# Solenoid_con.net
KiCad netlist of a schematic drawn in EAGLE
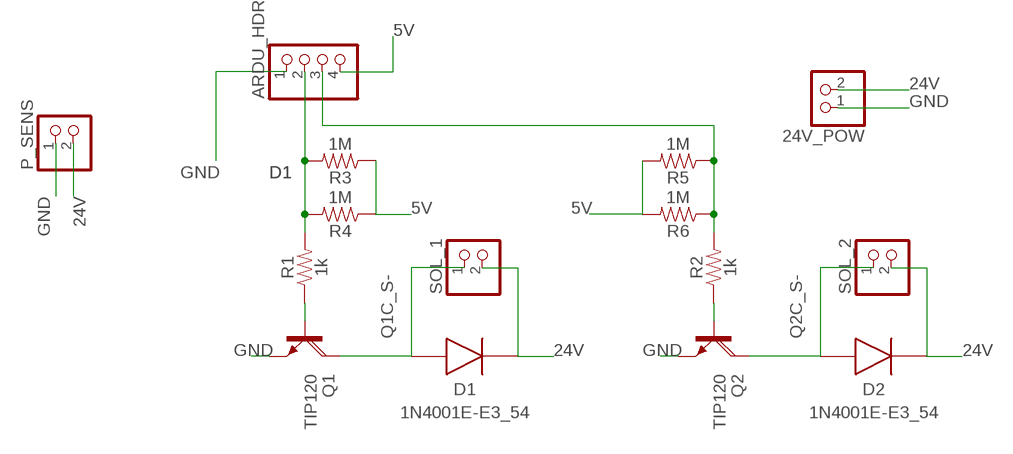
[diagram p0: schematic, sheet 1]

(export (version "E")
  (design (tool "Eeschema 10.0.6"))
  (components
    (comp (ref "24V_POW")
      (value "PINHD-1X2")
      (footprint "eagle-import:1X02")
      (libsource (lib "eagle-import") (part "PINHD-1X2"))
    )
    (comp (ref "ARDU_HDR")
      (value "PINHD-1X4")
      (footprint "eagle-import:1X04")
      (libsource (lib "eagle-import") (part "PINHD-1X4"))
    )
    (comp (ref "D1")
      (value "1N4001E-E3_54")
      (footprint "eagle-import:DIOAD1405W86L465D235")
      (fields (field (name "MANUFACTURER_PART_NUMBER") "1N4001E-E3/54"))
      (libsource (lib "eagle-import") (part "1N4001E-E3_54"))
    )
    (comp (ref "D2")
      (value "1N4001E-E3_54")
      (footprint "eagle-import:DIOAD1405W86L465D235")
      (fields (field (name "MANUFACTURER_PART_NUMBER") "1N4001E-E3/54"))
      (libsource (lib "eagle-import") (part "1N4001E-E3_54"))
    )
    (comp (ref "P_SENS")
      (value "PINHD-1X2")
      (footprint "eagle-import:1X02")
      (libsource (lib "eagle-import") (part "PINHD-1X2"))
    )
    (comp (ref "Q1")
      (value "TIP120")
      (footprint "eagle-import:TO220AH")
      (libsource (lib "eagle-import") (part "TIP120"))
    )
    (comp (ref "Q2")
      (value "TIP120")
      (footprint "eagle-import:TO220AH")
      (libsource (lib "eagle-import") (part "TIP120"))
    )
    (comp (ref "R1")
      (value "1k")
      (footprint "eagle-import:AXIAL-0.3")
      (libsource (lib "eagle-import") (part "1KOHM-HORIZ-1/4W-5%"))
    )
    (comp (ref "R2")
      (value "1k")
      (footprint "eagle-import:AXIAL-0.3")
      (libsource (lib "eagle-import") (part "1KOHM-HORIZ-1/4W-5%"))
    )
    (comp (ref "R3")
      (value "1M")
      (footprint "eagle-import:AXIAL-0.3")
      (libsource (lib "eagle-import") (part "1KOHM-HORIZ-1/4W-5%"))
    )
    (comp (ref "R4")
      (value "1M")
      (footprint "eagle-import:AXIAL-0.3")
      (libsource (lib "eagle-import") (part "1KOHM-HORIZ-1/4W-5%"))
    )
    (comp (ref "R5")
      (value "1M")
      (footprint "eagle-import:AXIAL-0.3")
      (libsource (lib "eagle-import") (part "1KOHM-HORIZ-1/4W-5%"))
    )
    (comp (ref "R6")
      (value "1M")
      (footprint "eagle-import:AXIAL-0.3")
      (libsource (lib "eagle-import") (part "1KOHM-HORIZ-1/4W-5%"))
    )
    (comp (ref "SOL_1")
      (value "PINHD-1X2")
      (footprint "eagle-import:1X02")
      (libsource (lib "eagle-import") (part "PINHD-1X2"))
    )
    (comp (ref "SOL_2")
      (value "PINHD-1X2")
      (footprint "eagle-import:1X02")
      (libsource (lib "eagle-import") (part "PINHD-1X2"))
    )
  )
  (nets
    (net (code "1") (name "/5V") (class "Default")
      (node (ref "ARDU_HDR") (pin "4") (pinfunction "4_4") (pintype "passive"))
      (node (ref "R3") (pin "P$1") (pinfunction "1_P$1") (pintype "passive"))
      (node (ref "R4") (pin "P$1") (pinfunction "1_P$1") (pintype "passive"))
      (node (ref "R5") (pin "P$2") (pinfunction "2_P$2") (pintype "passive"))
      (node (ref "R6") (pin "P$2") (pinfunction "2_P$2") (pintype "passive"))
    )
    (net (code "2") (name "/24V") (class "Default")
      (node (ref "24V_POW") (pin "2") (pinfunction "2_2") (pintype "passive"))
      (node (ref "D1") (pin "2") (pinfunction "K_2") (pintype "bidirectional"))
      (node (ref "D2") (pin "2") (pinfunction "K_2") (pintype "bidirectional"))
      (node (ref "P_SENS") (pin "2") (pinfunction "2_2") (pintype "passive"))
      (node (ref "SOL_1") (pin "2") (pinfunction "2_2") (pintype "passive"))
      (node (ref "SOL_2") (pin "2") (pinfunction "2_2") (pintype "passive"))
    )
    (net (code "3") (name "/D1") (class "Default")
      (node (ref "ARDU_HDR") (pin "2") (pinfunction "2_2") (pintype "passive"))
      (node (ref "R1") (pin "P$2") (pinfunction "2_P$2") (pintype "passive"))
      (node (ref "R3") (pin "P$2") (pinfunction "2_P$2") (pintype "passive"))
      (node (ref "R4") (pin "P$2") (pinfunction "2_P$2") (pintype "passive"))
    )
    (net (code "4") (name "/GND") (class "Default")
      (node (ref "24V_POW") (pin "1") (pinfunction "1_1") (pintype "passive"))
      (node (ref "ARDU_HDR") (pin "1") (pinfunction "1_1") (pintype "passive"))
      (node (ref "P_SENS") (pin "1") (pinfunction "1_1") (pintype "passive"))
      (node (ref "Q1") (pin "E") (pinfunction "E_E") (pintype "passive"))
      (node (ref "Q2") (pin "E") (pinfunction "E_E") (pintype "passive"))
    )
    (net (code "5") (name "/Q1C_S-") (class "Default")
      (node (ref "D1") (pin "1") (pinfunction "A_1") (pintype "bidirectional"))
      (node (ref "Q1") (pin "C") (pinfunction "C_C") (pintype "passive"))
      (node (ref "SOL_1") (pin "1") (pinfunction "1_1") (pintype "passive"))
    )
    (net (code "6") (name "/Q2C_S-") (class "Default")
      (node (ref "D2") (pin "1") (pinfunction "A_1") (pintype "bidirectional"))
      (node (ref "Q2") (pin "C") (pinfunction "C_C") (pintype "passive"))
      (node (ref "SOL_2") (pin "1") (pinfunction "1_1") (pintype "passive"))
    )
    (net (code "7") (name "Net-(R1-1)") (class "Default")
      (node (ref "Q1") (pin "B") (pinfunction "B_B") (pintype "passive"))
      (node (ref "R1") (pin "P$1") (pinfunction "1_P$1") (pintype "passive"))
    )
    (net (code "8") (name "Net-(R2-1)") (class "Default")
      (node (ref "Q2") (pin "B") (pinfunction "B_B") (pintype "passive"))
      (node (ref "R2") (pin "P$1") (pinfunction "1_P$1") (pintype "passive"))
    )
    (net (code "9") (name "Net-(R2-2)") (class "Default")
      (node (ref "ARDU_HDR") (pin "3") (pinfunction "3_3") (pintype "passive"))
      (node (ref "R2") (pin "P$2") (pinfunction "2_P$2") (pintype "passive"))
      (node (ref "R5") (pin "P$1") (pinfunction "1_P$1") (pintype "passive"))
      (node (ref "R6") (pin "P$1") (pinfunction "1_P$1") (pintype "passive"))
    )
  )
)
